# Sch_Dr_NPX.net
KiCad netlist of a schematic drawn in Altium Designer
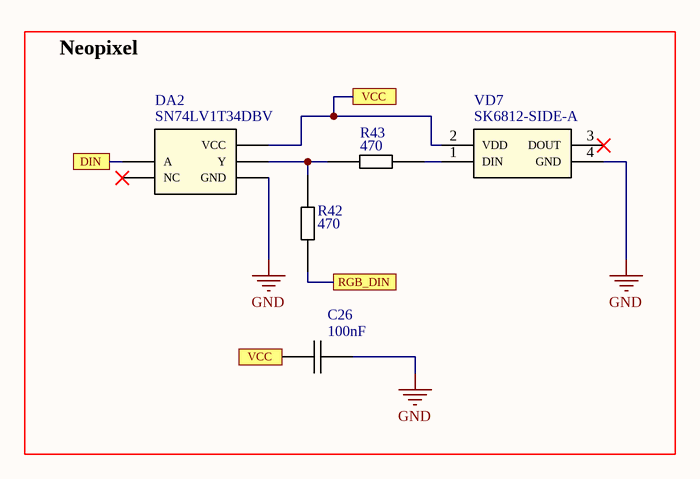
[diagram p0: Sch_Dr_NPX .SchDoc]

(export (version "E")
  (design (tool "Eeschema 10.0.6"))
  (components
    (comp (ref "C26")
      (value "100nF")
      (footprint "Cap_0603")
      (description "CC0603JRX7R8BB104")
      (libsource (lib "Dr_lib") (part "Cap_"))
    )
    (comp (ref "DA2")
      (value "SN74LV1T34DBV")
      (footprint "SOT-23-5")
      (description "Single Power Supply Single Buffer GATE CMOS Logic Level Sgifter")
      (libsource (lib "Dr_lib") (part "SN74LV1T34DBV"))
    )
    (comp (ref "R42")
      (value "470")
      (footprint "Res_0603")
      (description "CR-03FL7--470R")
      (libsource (lib "") (part "Res__1"))
    )
    (comp (ref "R43")
      (value "470")
      (footprint "Res_0603")
      (description "CR-03FL7--470R")
      (libsource (lib "Dr_lib") (part "Res_"))
    )
    (comp (ref "VD7")
      (value "SK6812-SIDE-A")
      (footprint "SK6812 (LED)")
      (description "LED chip")
      (libsource (lib "Dr_lib") (part "SK6812-SIDE-A"))
    )
  )
  (nets
    (net (code "1") (name "/DIN") (class "Default")
      (node (ref "DA2") (pin "2") (pinfunction "A_2") (pintype "passive"))
    )
    (net (code "2") (name "/RGB_DIN") (class "Default")
      (node (ref "R42") (pin "1") (pinfunction "1_1") (pintype "passive"))
    )
    (net (code "3") (name "/VCC") (class "Default")
      (node (ref "C26") (pin "1") (pinfunction "1_1") (pintype "passive"))
      (node (ref "DA2") (pin "5") (pinfunction "VCC_5") (pintype "passive"))
      (node (ref "VD7") (pin "2") (pinfunction "VDD_2") (pintype "passive"))
    )
    (net (code "4") (name "GND") (class "Default")
      (node (ref "C26") (pin "2") (pinfunction "2_2") (pintype "passive"))
      (node (ref "DA2") (pin "3") (pinfunction "GND_3") (pintype "passive"))
      (node (ref "VD7") (pin "4") (pinfunction "GND_4") (pintype "passive"))
    )
    (net (code "5") (name "Net-(DA2-Y)") (class "Default")
      (node (ref "DA2") (pin "4") (pinfunction "Y_4") (pintype "passive"))
      (node (ref "R42") (pin "2") (pinfunction "2_2") (pintype "passive"))
      (node (ref "R43") (pin "1") (pinfunction "1_1") (pintype "passive"))
    )
    (net (code "6") (name "Net-(VD7-DIN)") (class "Default")
      (node (ref "R43") (pin "2") (pinfunction "2_2") (pintype "passive"))
      (node (ref "VD7") (pin "1") (pinfunction "DIN_1") (pintype "passive"))
    )
    (net (code "7") (name "unconnected-(DA2-NC-Pad1)") (class "Default")
      (node (ref "DA2") (pin "1") (pinfunction "NC_1") (pintype "passive+no_connect"))
    )
    (net (code "8") (name "unconnected-(VD7-DOUT-Pad3)") (class "Default")
      (node (ref "VD7") (pin "3") (pinfunction "DOUT_3") (pintype "passive+no_connect"))
    )
  )
)
